# MCU.net
KiCad netlist of a schematic drawn in Altium Designer
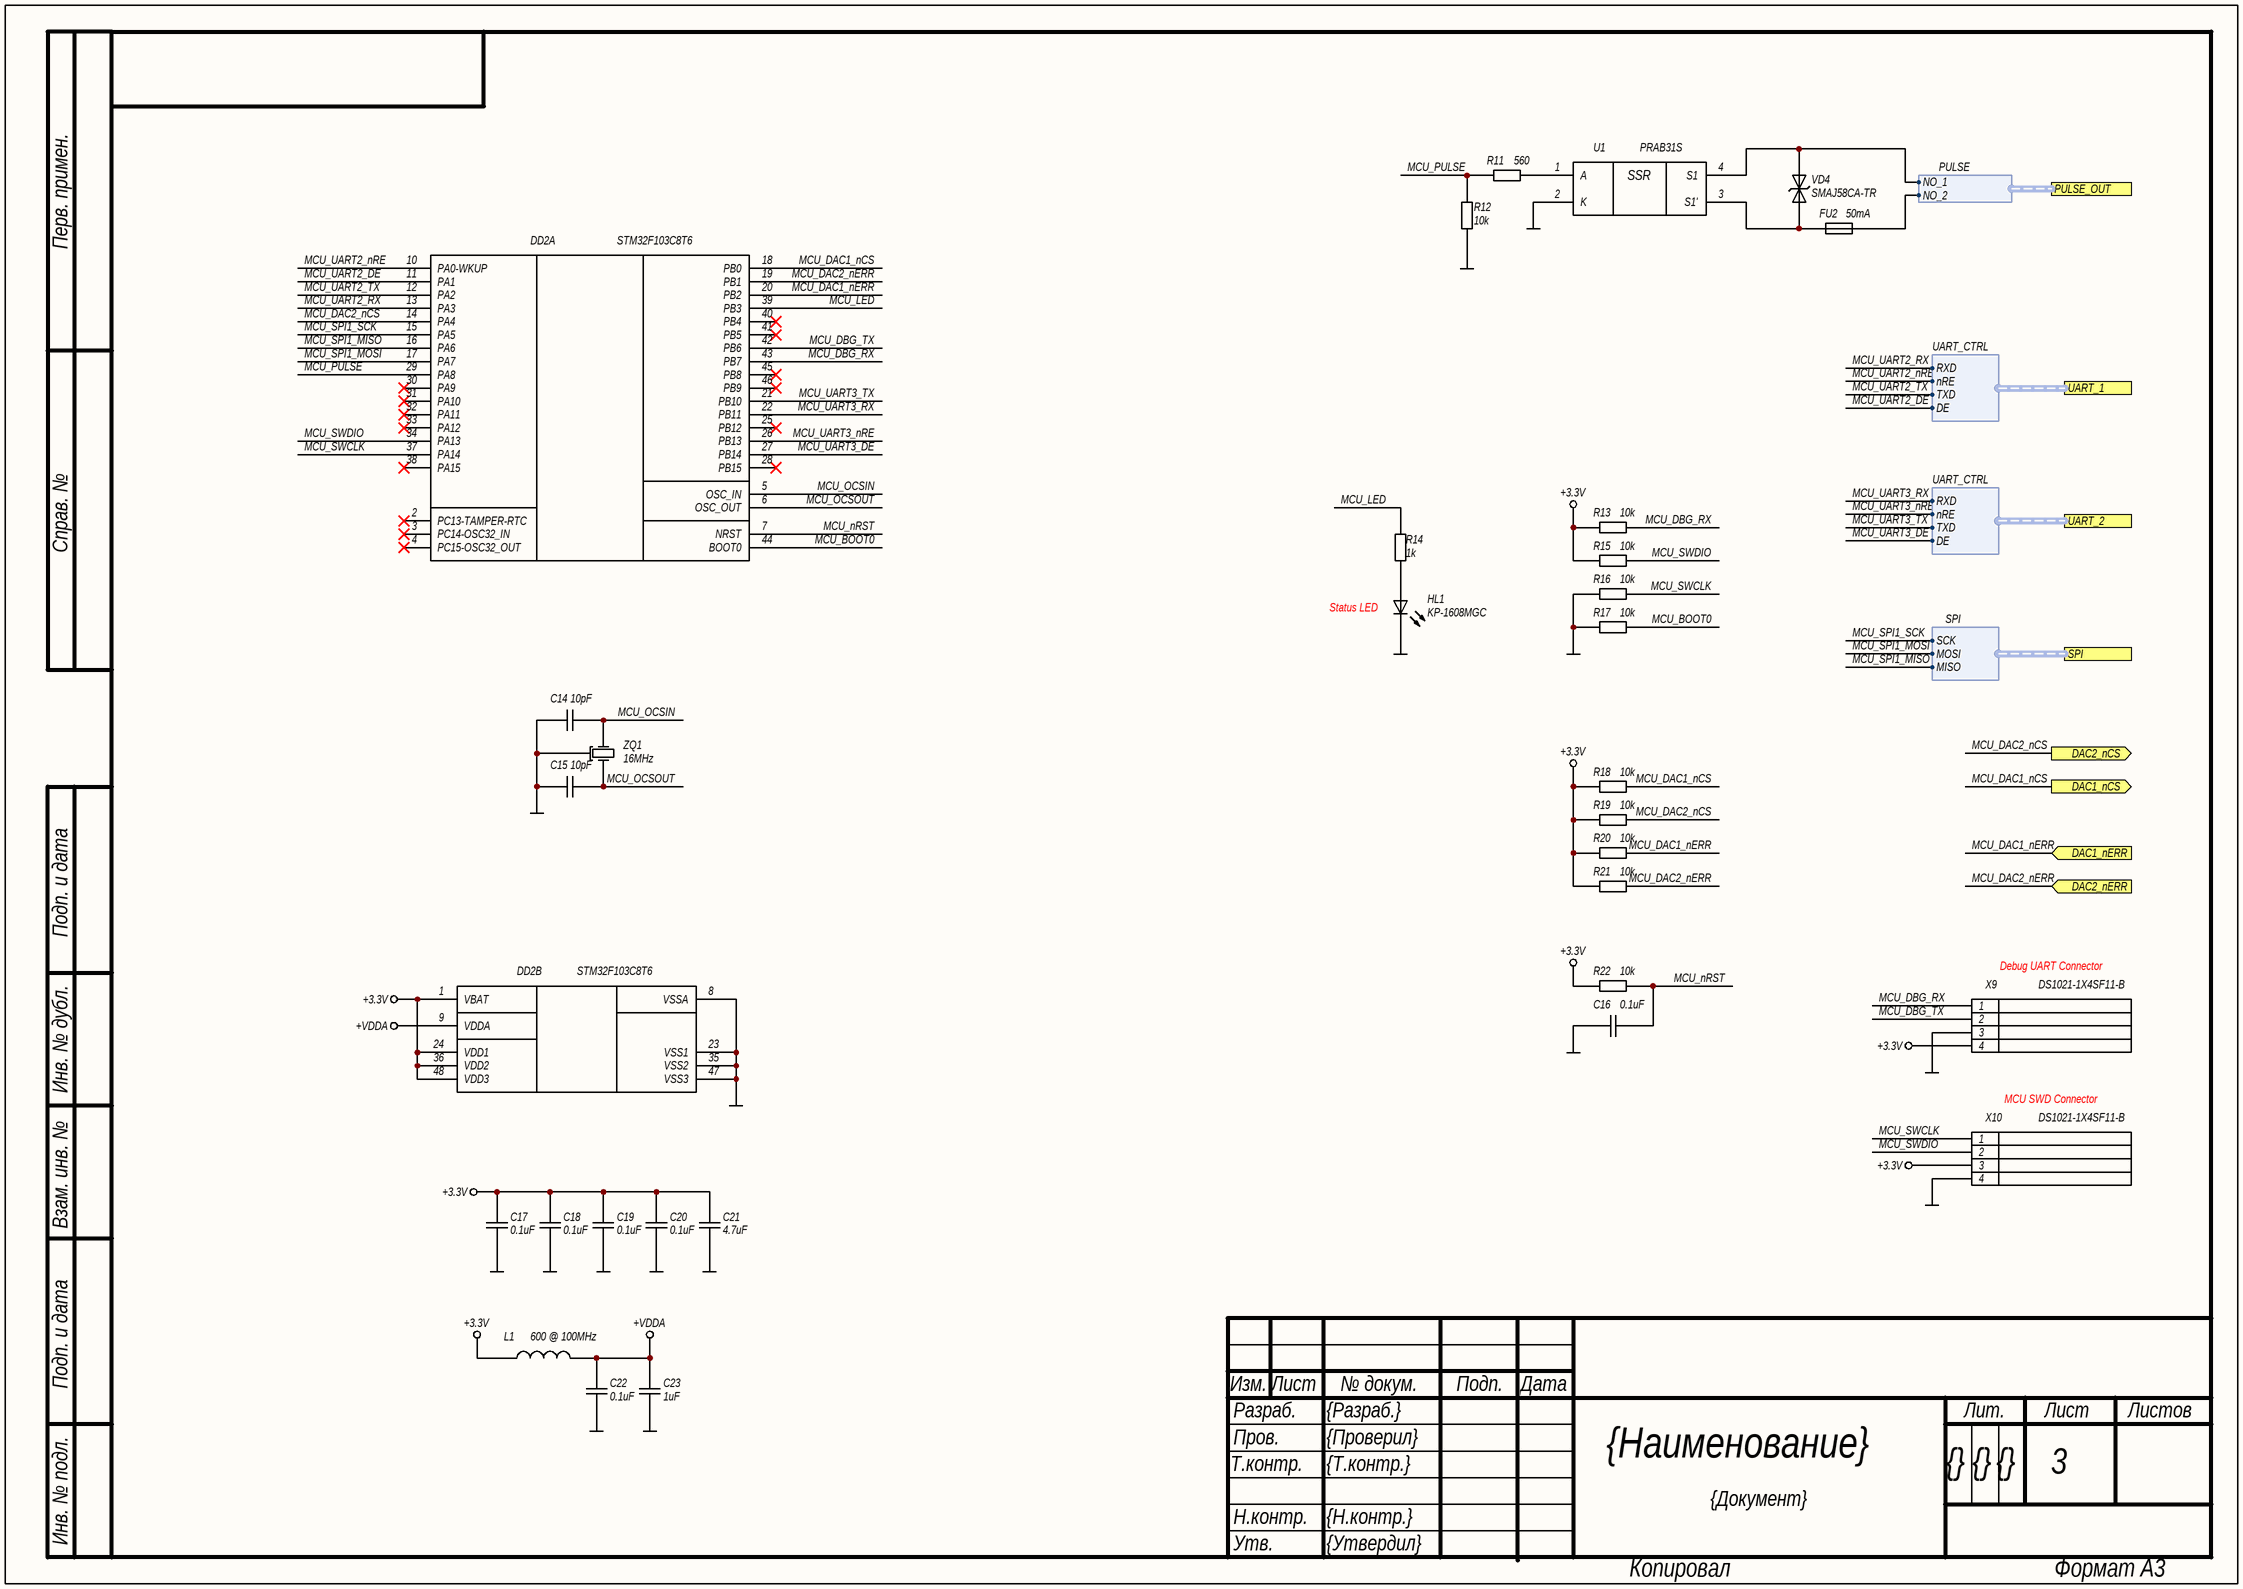
[diagram p0: MCU.SchDoc]

(export (version "E")
  (design (tool "Eeschema 10.0.6"))
  (components
    (comp (ref "C14")
      (value "10pF")
      (footprint "C0603N")
      (description "Конденсатор")
      (libsource (lib "Components Library") (part "CAP_FIXED"))
    )
    (comp (ref "C15")
      (value "10pF")
      (footprint "C0603N")
      (description "Конденсатор")
      (libsource (lib "Components Library") (part "CAP_FIXED"))
    )
    (comp (ref "C16")
      (value "0.1uF")
      (footprint "C0603N")
      (description "Конденсатор")
      (libsource (lib "Components Library") (part "CAP_FIXED"))
    )
    (comp (ref "C17")
      (value "0.1uF")
      (footprint "C0603N")
      (description "Конденсатор")
      (libsource (lib "Components Library") (part "CAP_FIXED"))
    )
    (comp (ref "C18")
      (value "0.1uF")
      (footprint "C0603N")
      (description "Конденсатор")
      (libsource (lib "Components Library") (part "CAP_FIXED"))
    )
    (comp (ref "C19")
      (value "0.1uF")
      (footprint "C0603N")
      (description "Конденсатор")
      (libsource (lib "Components Library") (part "CAP_FIXED"))
    )
    (comp (ref "C20")
      (value "0.1uF")
      (footprint "C0603N")
      (description "Конденсатор")
      (libsource (lib "Components Library") (part "CAP_FIXED"))
    )
    (comp (ref "C21")
      (value "4.7uF")
      (footprint "C0805N")
      (description "Конденсатор")
      (libsource (lib "Components Library") (part "CAP_FIXED"))
    )
    (comp (ref "C22")
      (value "0.1uF")
      (footprint "C0603N")
      (description "Конденсатор")
      (libsource (lib "Components Library") (part "CAP_FIXED"))
    )
    (comp (ref "C23")
      (value "1uF")
      (footprint "C0603N")
      (description "Конденсатор")
      (libsource (lib "Components Library") (part "CAP_FIXED"))
    )
    (comp (ref "DD2")
      (value "STM32F103C8T6")
      (footprint "LQFP48")
      (description "Микросхема микроконтроллер")
      (libsource (lib "Components Library") (part "STM32F103Cx"))
    )
    (comp (ref "FU2")
      (value "50mA")
      (footprint "0ZCJ_0.85")
      (description "Плавкий предохранитель")
      (libsource (lib "Components Library") (part "FUSE"))
    )
    (comp (ref "HL1")
      (value "KP-1608MGC")
      (footprint "LED0603")
      (description "Светодиод")
      (libsource (lib "Components Library") (part "LED"))
    )
    (comp (ref "L1")
      (value "600 @ 100MHz")
      (footprint "FB0603N")
      (description "Фильтр ЭМП индуктивный")
      (libsource (lib "Components Library") (part "IND_FILTER"))
    )
    (comp (ref "R11")
      (value "560")
      (footprint "R0603N")
      (description "Резистор")
      (libsource (lib "Components Library") (part "RES_FIXED"))
    )
    (comp (ref "R12")
      (value "10k")
      (footprint "R0603N")
      (description "Резистор")
      (libsource (lib "") (part "RES_FIXED_1"))
    )
    (comp (ref "R13")
      (value "10k")
      (footprint "R0603N")
      (description "Резистор")
      (libsource (lib "Components Library") (part "RES_FIXED"))
    )
    (comp (ref "R14")
      (value "1k")
      (footprint "R0603N")
      (description "Резистор")
      (libsource (lib "") (part "RES_FIXED_1"))
    )
    (comp (ref "R15")
      (value "10k")
      (footprint "R0603N")
      (description "Резистор")
      (libsource (lib "Components Library") (part "RES_FIXED"))
    )
    (comp (ref "R16")
      (value "10k")
      (footprint "R0603N")
      (description "Резистор")
      (libsource (lib "Components Library") (part "RES_FIXED"))
    )
    (comp (ref "R17")
      (value "10k")
      (footprint "R0603N")
      (description "Резистор")
      (libsource (lib "Components Library") (part "RES_FIXED"))
    )
    (comp (ref "R18")
      (value "10k")
      (footprint "R0603N")
      (description "Резистор")
      (libsource (lib "Components Library") (part "RES_FIXED"))
    )
    (comp (ref "R19")
      (value "10k")
      (footprint "R0603N")
      (description "Резистор")
      (libsource (lib "Components Library") (part "RES_FIXED"))
    )
    (comp (ref "R20")
      (value "10k")
      (footprint "R0603N")
      (description "Резистор")
      (libsource (lib "Components Library") (part "RES_FIXED"))
    )
    (comp (ref "R21")
      (value "10k")
      (footprint "R0603N")
      (description "Резистор")
      (libsource (lib "Components Library") (part "RES_FIXED"))
    )
    (comp (ref "R22")
      (value "10k")
      (footprint "R0603N")
      (description "Резистор")
      (libsource (lib "Components Library") (part "RES_FIXED"))
    )
    (comp (ref "U1")
      (value "PRAB31S")
      (footprint "SOP4")
      (description "Твердотельное реле, SPST-NO")
      (libsource (lib "Components Library") (part "PRAx_1A_NO"))
    )
    (comp (ref "VD4")
      (value "SMAJ58CA-TR")
      (footprint "SMA")
      (description "TVS диод двунаправленный")
      (libsource (lib "Components Library") (part "TVS_BIDIR"))
    )
    (comp (ref "X9")
      (value "DS1021-1X4SF11-B")
      (footprint "2.54_1X4_HEADER")
      (description "Разъем, 4 контакта")
      (libsource (lib "Components Library") (part "Connector 4"))
    )
    (comp (ref "X10")
      (value "DS1021-1X4SF11-B")
      (footprint "2.54_1X4_HEADER")
      (description "Разъем, 4 контакта")
      (libsource (lib "Components Library") (part "Connector 4"))
    )
    (comp (ref "ZQ1")
      (value "16MHz")
      (footprint "NX3225GA")
      (description "Кварцевый резонатор, экранированный")
      (libsource (lib "Components Library") (part "RESONATOR_3PIN"))
    )
  )
  (nets
    (net (code "4") (name "+3.3V") (class "Default")
      (node (ref "C17") (pin "2") (pinfunction "2_2") (pintype "passive"))
      (node (ref "C18") (pin "2") (pinfunction "2_2") (pintype "passive"))
      (node (ref "C19") (pin "2") (pinfunction "2_2") (pintype "passive"))
      (node (ref "C20") (pin "2") (pinfunction "2_2") (pintype "passive"))
      (node (ref "C21") (pin "2") (pinfunction "2_2") (pintype "passive"))
      (node (ref "DD2") (pin "1") (pinfunction "VBAT_1") (pintype "passive"))
      (node (ref "DD2") (pin "24") (pinfunction "VDD1_24") (pintype "passive"))
      (node (ref "DD2") (pin "36") (pinfunction "VDD2_36") (pintype "passive"))
      (node (ref "DD2") (pin "48") (pinfunction "VDD3_48") (pintype "passive"))
      (node (ref "L1") (pin "1") (pinfunction "1_1") (pintype "passive"))
      (node (ref "R13") (pin "2") (pinfunction "2_2") (pintype "passive"))
      (node (ref "R15") (pin "2") (pinfunction "2_2") (pintype "passive"))
      (node (ref "R18") (pin "2") (pinfunction "2_2") (pintype "passive"))
      (node (ref "R19") (pin "2") (pinfunction "2_2") (pintype "passive"))
      (node (ref "R20") (pin "2") (pinfunction "2_2") (pintype "passive"))
      (node (ref "R21") (pin "2") (pinfunction "2_2") (pintype "passive"))
      (node (ref "R22") (pin "2") (pinfunction "2_2") (pintype "passive"))
      (node (ref "X10") (pin "3") (pinfunction "3_3") (pintype "power_in"))
      (node (ref "X9") (pin "4") (pinfunction "4_4") (pintype "power_in"))
    )
    (net (code "5") (name "+VDDA") (class "Default")
      (node (ref "C22") (pin "2") (pinfunction "2_2") (pintype "passive"))
      (node (ref "C23") (pin "1") (pinfunction "1_1") (pintype "passive"))
      (node (ref "DD2") (pin "9") (pinfunction "VDDA_9") (pintype "passive"))
      (node (ref "L1") (pin "2") (pinfunction "2_2") (pintype "passive"))
    )
    (net (code "6") (name "/MCU_BOOT0") (class "Default")
      (node (ref "DD2") (pin "44") (pinfunction "BOOT0_44") (pintype "passive"))
      (node (ref "R17") (pin "1") (pinfunction "1_1") (pintype "passive"))
    )
    (net (code "7") (name "/MCU_DAC1_nCS") (class "Default")
      (node (ref "DD2") (pin "18") (pinfunction "PB0_18") (pintype "passive"))
      (node (ref "R18") (pin "1") (pinfunction "1_1") (pintype "passive"))
    )
    (net (code "8") (name "/MCU_DAC1_nERR") (class "Default")
      (node (ref "DD2") (pin "20") (pinfunction "PB2_20") (pintype "passive"))
      (node (ref "R20") (pin "1") (pinfunction "1_1") (pintype "passive"))
    )
    (net (code "9") (name "/MCU_DAC2_nCS") (class "Default")
      (node (ref "DD2") (pin "14") (pinfunction "PA4_14") (pintype "passive"))
      (node (ref "R19") (pin "1") (pinfunction "1_1") (pintype "passive"))
    )
    (net (code "10") (name "/MCU_DAC2_nERR") (class "Default")
      (node (ref "DD2") (pin "19") (pinfunction "PB1_19") (pintype "passive"))
      (node (ref "R21") (pin "1") (pinfunction "1_1") (pintype "passive"))
    )
    (net (code "11") (name "/MCU_DBG_RX") (class "Default")
      (node (ref "DD2") (pin "43") (pinfunction "PB7_43") (pintype "passive"))
      (node (ref "R13") (pin "1") (pinfunction "1_1") (pintype "passive"))
      (node (ref "X9") (pin "1") (pinfunction "1_1") (pintype "power_in"))
    )
    (net (code "12") (name "/MCU_DBG_TX") (class "Default")
      (node (ref "DD2") (pin "42") (pinfunction "PB6_42") (pintype "passive"))
      (node (ref "X9") (pin "2") (pinfunction "2_2") (pintype "power_in"))
    )
    (net (code "13") (name "/MCU_LED") (class "Default")
      (node (ref "DD2") (pin "39") (pinfunction "PB3_39") (pintype "passive"))
      (node (ref "R14") (pin "1") (pinfunction "1_1") (pintype "passive"))
    )
    (net (code "14") (name "/MCU_OCSIN") (class "Default")
      (node (ref "C14") (pin "1") (pinfunction "1_1") (pintype "passive"))
      (node (ref "DD2") (pin "5") (pinfunction "OSC_IN_5") (pintype "passive"))
      (node (ref "ZQ1") (pin "3") (pinfunction "3_3") (pintype "passive"))
    )
    (net (code "15") (name "/MCU_OCSOUT") (class "Default")
      (node (ref "C15") (pin "1") (pinfunction "1_1") (pintype "passive"))
      (node (ref "DD2") (pin "6") (pinfunction "OSC_OUT_6") (pintype "passive"))
      (node (ref "ZQ1") (pin "1") (pinfunction "1_1") (pintype "passive"))
    )
    (net (code "16") (name "/MCU_PULSE") (class "Default")
      (node (ref "DD2") (pin "29") (pinfunction "PA8_29") (pintype "passive"))
      (node (ref "R11") (pin "2") (pinfunction "2_2") (pintype "passive"))
      (node (ref "R12") (pin "1") (pinfunction "1_1") (pintype "passive"))
    )
    (net (code "17") (name "/MCU_SPI1_MISO") (class "Default")
      (node (ref "DD2") (pin "16") (pinfunction "PA6_16") (pintype "passive"))
    )
    (net (code "18") (name "/MCU_SPI1_MOSI") (class "Default")
      (node (ref "DD2") (pin "17") (pinfunction "PA7_17") (pintype "passive"))
    )
    (net (code "19") (name "/MCU_SPI1_SCK") (class "Default")
      (node (ref "DD2") (pin "15") (pinfunction "PA5_15") (pintype "passive"))
    )
    (net (code "20") (name "/MCU_SWCLK") (class "Default")
      (node (ref "DD2") (pin "37") (pinfunction "PA14_37") (pintype "passive"))
      (node (ref "R16") (pin "1") (pinfunction "1_1") (pintype "passive"))
      (node (ref "X10") (pin "1") (pinfunction "1_1") (pintype "power_in"))
    )
    (net (code "21") (name "/MCU_SWDIO") (class "Default")
      (node (ref "DD2") (pin "34") (pinfunction "PA13_34") (pintype "passive"))
      (node (ref "R15") (pin "1") (pinfunction "1_1") (pintype "passive"))
      (node (ref "X10") (pin "2") (pinfunction "2_2") (pintype "power_in"))
    )
    (net (code "22") (name "/MCU_UART2_DE") (class "Default")
      (node (ref "DD2") (pin "11") (pinfunction "PA1_11") (pintype "passive"))
    )
    (net (code "23") (name "/MCU_UART2_RX") (class "Default")
      (node (ref "DD2") (pin "13") (pinfunction "PA3_13") (pintype "passive"))
    )
    (net (code "24") (name "/MCU_UART2_TX") (class "Default")
      (node (ref "DD2") (pin "12") (pinfunction "PA2_12") (pintype "passive"))
    )
    (net (code "25") (name "/MCU_UART2_nRE") (class "Default")
      (node (ref "DD2") (pin "10") (pinfunction "PA0-WKUP_10") (pintype "passive"))
    )
    (net (code "26") (name "/MCU_UART3_DE") (class "Default")
      (node (ref "DD2") (pin "27") (pinfunction "PB14_27") (pintype "passive"))
    )
    (net (code "27") (name "/MCU_UART3_RX") (class "Default")
      (node (ref "DD2") (pin "22") (pinfunction "PB11_22") (pintype "passive"))
    )
    (net (code "28") (name "/MCU_UART3_TX") (class "Default")
      (node (ref "DD2") (pin "21") (pinfunction "PB10_21") (pintype "passive"))
    )
    (net (code "29") (name "/MCU_UART3_nRE") (class "Default")
      (node (ref "DD2") (pin "26") (pinfunction "PB13_26") (pintype "passive"))
    )
    (net (code "30") (name "/MCU_nRST") (class "Default")
      (node (ref "C16") (pin "1") (pinfunction "1_1") (pintype "passive"))
      (node (ref "DD2") (pin "7") (pinfunction "NRST_7") (pintype "passive"))
      (node (ref "R22") (pin "1") (pinfunction "1_1") (pintype "passive"))
    )
    (net (code "31") (name "/NO_1") (class "Default")
      (node (ref "U1") (pin "4") (pinfunction "S1_4") (pintype "power_in"))
      (node (ref "VD4") (pin "1") (pinfunction "A1_1") (pintype "passive"))
    )
    (net (code "32") (name "/NO_2") (class "Default")
      (node (ref "FU2") (pin "1") (pinfunction "1_1") (pintype "passive"))
    )
    (net (code "36") (name "GND") (class "Default")
      (node (ref "C14") (pin "2") (pinfunction "2_2") (pintype "passive"))
      (node (ref "C15") (pin "2") (pinfunction "2_2") (pintype "passive"))
      (node (ref "C16") (pin "2") (pinfunction "2_2") (pintype "passive"))
      (node (ref "C17") (pin "1") (pinfunction "1_1") (pintype "passive"))
      (node (ref "C18") (pin "1") (pinfunction "1_1") (pintype "passive"))
      (node (ref "C19") (pin "1") (pinfunction "1_1") (pintype "passive"))
      (node (ref "C20") (pin "1") (pinfunction "1_1") (pintype "passive"))
      (node (ref "C21") (pin "1") (pinfunction "1_1") (pintype "passive"))
      (node (ref "C22") (pin "1") (pinfunction "1_1") (pintype "passive"))
      (node (ref "C23") (pin "2") (pinfunction "2_2") (pintype "passive"))
      (node (ref "DD2") (pin "23") (pinfunction "VSS1_23") (pintype "passive"))
      (node (ref "DD2") (pin "35") (pinfunction "VSS2_35") (pintype "passive"))
      (node (ref "DD2") (pin "47") (pinfunction "VSS3_47") (pintype "passive"))
      (node (ref "DD2") (pin "8") (pinfunction "VSSA_8") (pintype "passive"))
      (node (ref "HL1") (pin "1") (pinfunction "K_1") (pintype "passive"))
      (node (ref "R12") (pin "2") (pinfunction "2_2") (pintype "passive"))
      (node (ref "R16") (pin "2") (pinfunction "2_2") (pintype "passive"))
      (node (ref "R17") (pin "2") (pinfunction "2_2") (pintype "passive"))
      (node (ref "U1") (pin "2") (pinfunction "K_2") (pintype "power_in"))
      (node (ref "X10") (pin "4") (pinfunction "4_4") (pintype "power_in"))
      (node (ref "X9") (pin "3") (pinfunction "3_3") (pintype "power_in"))
      (node (ref "ZQ1") (pin "2") (pinfunction "2_2") (pintype "passive"))
    )
    (net (code "37") (name "Net-(HL1-A)") (class "Default")
      (node (ref "HL1") (pin "2") (pinfunction "A_2") (pintype "passive"))
      (node (ref "R14") (pin "2") (pinfunction "2_2") (pintype "passive"))
    )
    (net (code "38") (name "Net-(U1-A)") (class "Default")
      (node (ref "R11") (pin "1") (pinfunction "1_1") (pintype "passive"))
      (node (ref "U1") (pin "1") (pinfunction "A_1") (pintype "power_in"))
    )
    (net (code "39") (name "Net-(U1-S1')") (class "Default")
      (node (ref "FU2") (pin "2") (pinfunction "2_2") (pintype "passive"))
      (node (ref "U1") (pin "3") (pinfunction "S1'_3") (pintype "power_in"))
      (node (ref "VD4") (pin "2") (pinfunction "A2_2") (pintype "passive"))
    )
    (net (code "40") (name "unconnected-(DD2A-PA9-Pad30)") (class "Default")
      (node (ref "DD2") (pin "30") (pinfunction "PA9_30") (pintype "passive+no_connect"))
    )
    (net (code "41") (name "unconnected-(DD2A-PA10-Pad31)") (class "Default")
      (node (ref "DD2") (pin "31") (pinfunction "PA10_31") (pintype "passive+no_connect"))
    )
    (net (code "42") (name "unconnected-(DD2A-PA11-Pad32)") (class "Default")
      (node (ref "DD2") (pin "32") (pinfunction "PA11_32") (pintype "passive+no_connect"))
    )
    (net (code "43") (name "unconnected-(DD2A-PA12-Pad33)") (class "Default")
      (node (ref "DD2") (pin "33") (pinfunction "PA12_33") (pintype "passive+no_connect"))
    )
    (net (code "44") (name "unconnected-(DD2A-PA15-Pad38)") (class "Default")
      (node (ref "DD2") (pin "38") (pinfunction "PA15_38") (pintype "passive+no_connect"))
    )
    (net (code "45") (name "unconnected-(DD2A-PB4-Pad40)") (class "Default")
      (node (ref "DD2") (pin "40") (pinfunction "PB4_40") (pintype "passive+no_connect"))
    )
    (net (code "46") (name "unconnected-(DD2A-PB5-Pad41)") (class "Default")
      (node (ref "DD2") (pin "41") (pinfunction "PB5_41") (pintype "passive+no_connect"))
    )
    (net (code "47") (name "unconnected-(DD2A-PB8-Pad45)") (class "Default")
      (node (ref "DD2") (pin "45") (pinfunction "PB8_45") (pintype "passive+no_connect"))
    )
    (net (code "48") (name "unconnected-(DD2A-PB9-Pad46)") (class "Default")
      (node (ref "DD2") (pin "46") (pinfunction "PB9_46") (pintype "passive+no_connect"))
    )
    (net (code "49") (name "unconnected-(DD2A-PB12-Pad25)") (class "Default")
      (node (ref "DD2") (pin "25") (pinfunction "PB12_25") (pintype "passive+no_connect"))
    )
    (net (code "50") (name "unconnected-(DD2A-PB15-Pad28)") (class "Default")
      (node (ref "DD2") (pin "28") (pinfunction "PB15_28") (pintype "passive+no_connect"))
    )
    (net (code "51") (name "unconnected-(DD2A-PC13-TAMPER-RTC-Pad2)") (class "Default")
      (node (ref "DD2") (pin "2") (pinfunction "PC13-TAMPER-RTC_2") (pintype "passive+no_connect"))
    )
    (net (code "52") (name "unconnected-(DD2A-PC14-OSC32_IN-Pad3)") (class "Default")
      (node (ref "DD2") (pin "3") (pinfunction "PC14-OSC32_IN_3") (pintype "passive+no_connect"))
    )
    (net (code "53") (name "unconnected-(DD2A-PC15-OSC32_OUT-Pad4)") (class "Default")
      (node (ref "DD2") (pin "4") (pinfunction "PC15-OSC32_OUT_4") (pintype "passive+no_connect"))
    )
  )
)
